# TouchPad.net
KiCad netlist of a schematic drawn in EAGLE
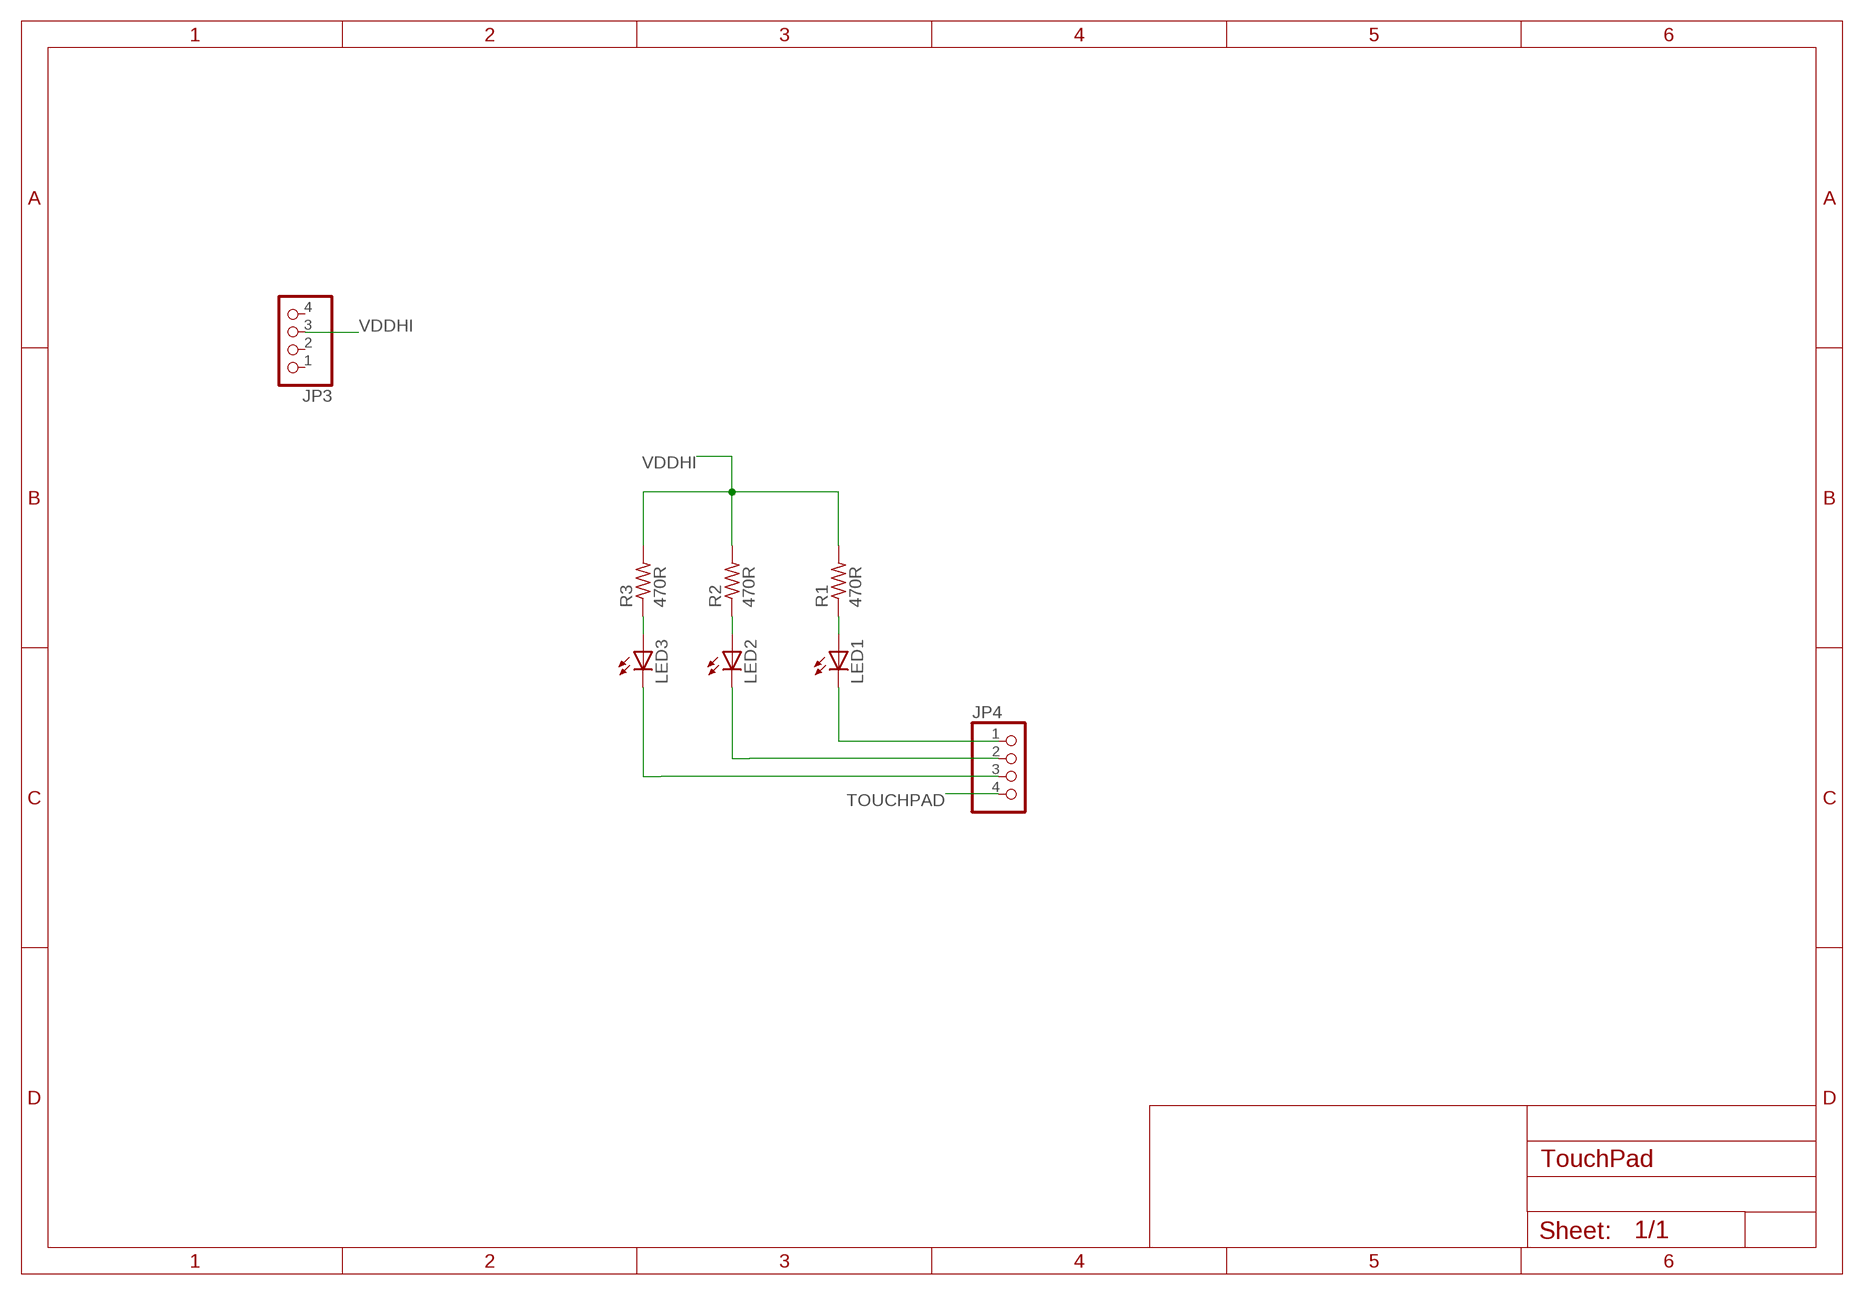
[diagram p0: schematic, sheet 1]

(export (version "E")
  (design (tool "Eeschema 10.0.6"))
  (components
    (comp (ref "JP3")
      (value "PINHD-1X4")
      (footprint "eagle-import:1X04")
      (libsource (lib "eagle-import") (part "PINHD-1X4"))
    )
    (comp (ref "JP4")
      (value "PINHD-1X4")
      (footprint "eagle-import:1X04")
      (libsource (lib "eagle-import") (part "PINHD-1X4"))
    )
    (comp (ref "LED1")
      (value "LEDCHIPLED_1206")
      (footprint "eagle-import:CHIPLED_1206")
      (libsource (lib "eagle-import") (part "LEDCHIPLED_1206"))
    )
    (comp (ref "LED2")
      (value "LEDCHIPLED_1206")
      (footprint "eagle-import:CHIPLED_1206")
      (libsource (lib "eagle-import") (part "LEDCHIPLED_1206"))
    )
    (comp (ref "LED3")
      (value "LEDCHIPLED_1206")
      (footprint "eagle-import:CHIPLED_1206")
      (libsource (lib "eagle-import") (part "LEDCHIPLED_1206"))
    )
    (comp (ref "R1")
      (value "470R")
      (footprint "eagle-import:R0603")
      (libsource (lib "eagle-import") (part "R-US_R0603"))
    )
    (comp (ref "R2")
      (value "470R")
      (footprint "eagle-import:R0603")
      (libsource (lib "eagle-import") (part "R-US_R0603"))
    )
    (comp (ref "R3")
      (value "470R")
      (footprint "eagle-import:R0603")
      (libsource (lib "eagle-import") (part "R-US_R0603"))
    )
  )
  (nets
    (net (code "1") (name "/TOUCHPAD") (class "Default")
      (node (ref "JP4") (pin "4") (pinfunction "4_4") (pintype "passive"))
    )
    (net (code "2") (name "/VDDHI") (class "Default")
      (node (ref "JP3") (pin "3") (pinfunction "3_3") (pintype "passive"))
      (node (ref "R1") (pin "2") (pinfunction "2_2") (pintype "passive"))
      (node (ref "R2") (pin "2") (pinfunction "2_2") (pintype "passive"))
      (node (ref "R3") (pin "2") (pinfunction "2_2") (pintype "passive"))
    )
    (net (code "3") (name "Net-(JP4-Pad1)") (class "Default")
      (node (ref "JP4") (pin "1") (pinfunction "1_1") (pintype "passive"))
      (node (ref "LED1") (pin "C") (pinfunction "C_C") (pintype "passive"))
    )
    (net (code "4") (name "Net-(JP4-Pad2)") (class "Default")
      (node (ref "JP4") (pin "2") (pinfunction "2_2") (pintype "passive"))
      (node (ref "LED2") (pin "C") (pinfunction "C_C") (pintype "passive"))
    )
    (net (code "5") (name "Net-(JP4-Pad3)") (class "Default")
      (node (ref "JP4") (pin "3") (pinfunction "3_3") (pintype "passive"))
      (node (ref "LED3") (pin "C") (pinfunction "C_C") (pintype "passive"))
    )
    (net (code "6") (name "Net-(LED1-PadA)") (class "Default")
      (node (ref "LED1") (pin "A") (pinfunction "A_A") (pintype "passive"))
      (node (ref "R1") (pin "1") (pinfunction "1_1") (pintype "passive"))
    )
    (net (code "7") (name "Net-(LED2-PadA)") (class "Default")
      (node (ref "LED2") (pin "A") (pinfunction "A_A") (pintype "passive"))
      (node (ref "R2") (pin "1") (pinfunction "1_1") (pintype "passive"))
    )
    (net (code "8") (name "Net-(LED3-PadA)") (class "Default")
      (node (ref "LED3") (pin "A") (pinfunction "A_A") (pintype "passive"))
      (node (ref "R3") (pin "1") (pinfunction "1_1") (pintype "passive"))
    )
    (net (code "9") (name "unconnected-(JP3-Pad1)") (class "Default")
      (node (ref "JP3") (pin "1") (pinfunction "1_1") (pintype "passive"))
    )
    (net (code "10") (name "unconnected-(JP3-Pad2)") (class "Default")
      (node (ref "JP3") (pin "2") (pinfunction "2_2") (pintype "passive"))
    )
    (net (code "11") (name "unconnected-(JP3-Pad4)") (class "Default")
      (node (ref "JP3") (pin "4") (pinfunction "4_4") (pintype "passive"))
    )
  )
)
